# Sheet3.net
KiCad netlist of a schematic drawn in Altium Designer
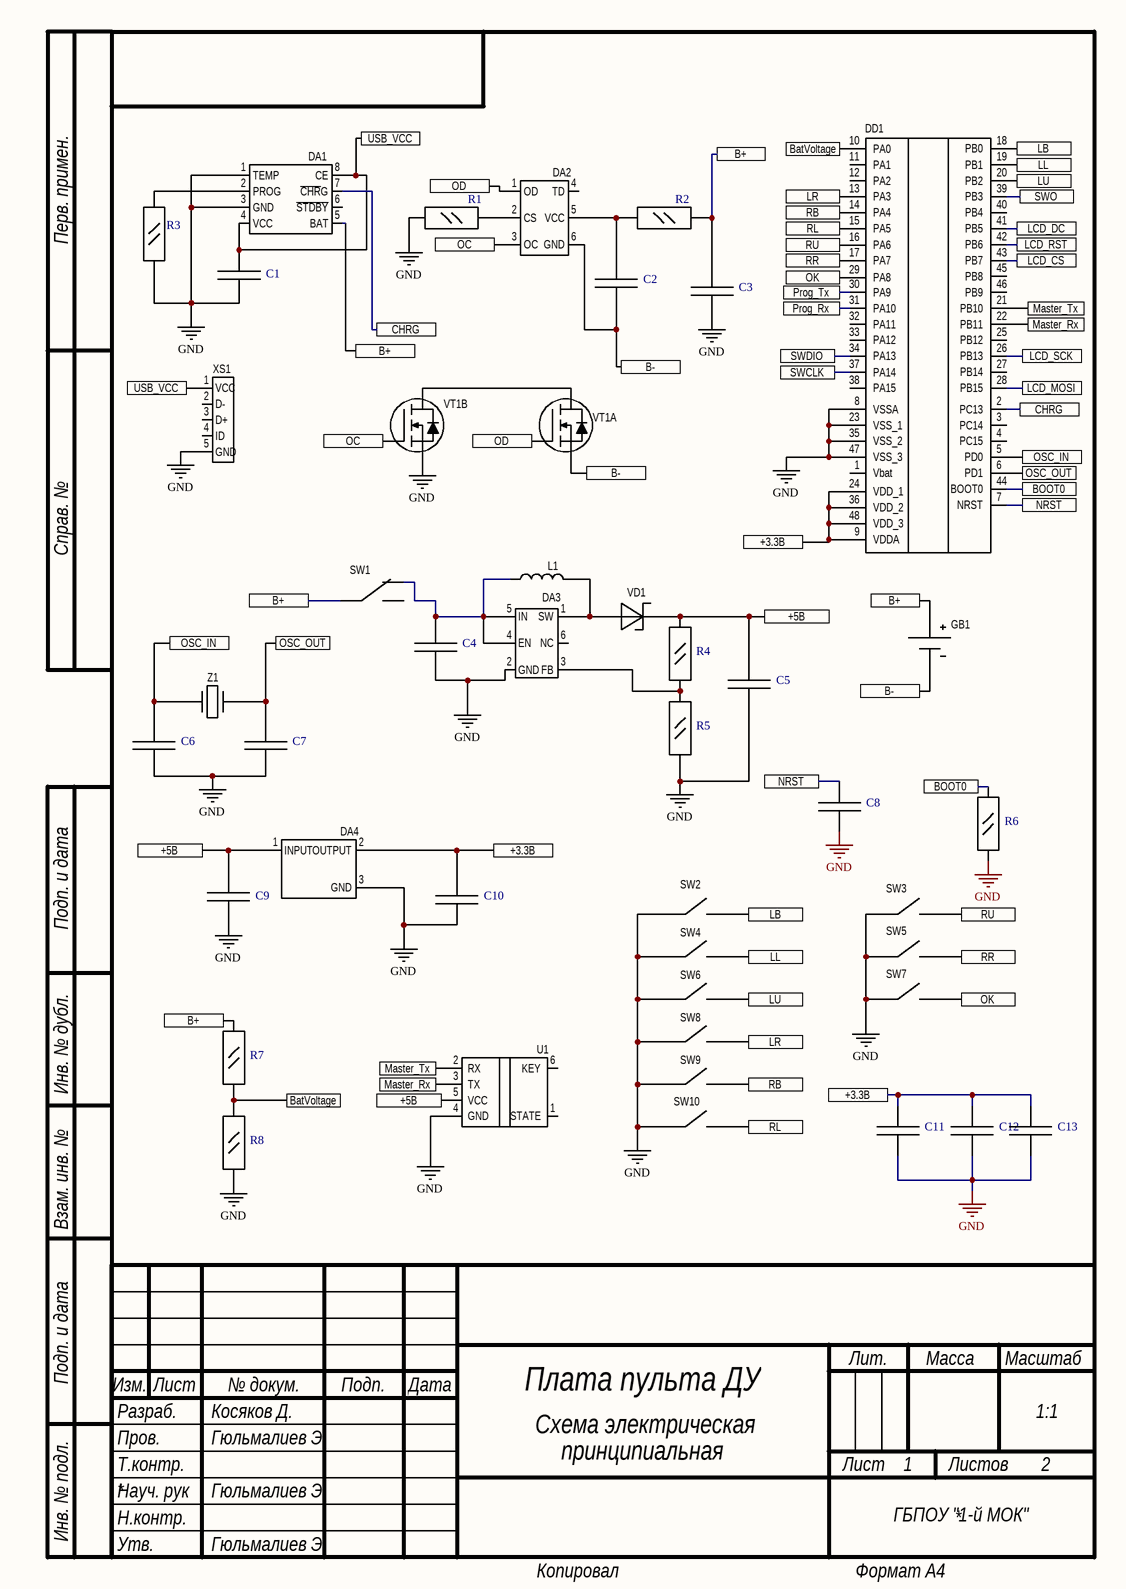
[diagram p0: Sheet3.SchDoc]

(export (version "E")
  (design (tool "Eeschema 10.0.6"))
  (components
    (comp (ref "C1") (value "0.1uF") (footprint "CAPC2112X13N") (libsource (lib "Schlib1") (part "0.1uF")))
    (comp (ref "C2") (value "0.1uF") (footprint "CAPC2112X13N") (libsource (lib "Schlib1") (part "0.1uF")))
    (comp (ref "C3") (value "10uF") (footprint "CAPC2112X13N") (libsource (lib "Schlib1") (part "0.1uF")))
    (comp (ref "C4") (value "22uF") (footprint "CAPC2112X13N") (libsource (lib "Schlib1") (part "0.1uF")))
    (comp (ref "C5") (value "22uF") (footprint "CAPC2112X13N") (libsource (lib "Schlib1") (part "0.1uF")))
    (comp (ref "C6") (value "22pF") (footprint "CAPC2112X13N") (libsource (lib "Schlib1") (part "0.1uF")))
    (comp (ref "C7") (value "22pF") (footprint "CAPC2112X13N") (libsource (lib "Schlib1") (part "0.1uF")))
    (comp (ref "C8") (value "0.1uF") (footprint "CAPC2112X13N") (libsource (lib "Schlib1") (part "0.1uF")))
    (comp (ref "C9") (value "10uF") (footprint "CAPC2112X13N") (libsource (lib "Schlib1") (part "0.1uF")))
    (comp (ref "C10") (value "10uF") (footprint "CAPC2112X13N") (libsource (lib "Schlib1") (part "0.1uF")))
    (comp (ref "C11") (value "0.1uF") (footprint "CAPC2112X13N") (libsource (lib "Schlib1") (part "0.1uF")))
    (comp (ref "C12") (value "0.1uF") (footprint "CAPC2112X13N") (libsource (lib "Schlib1") (part "0.1uF")))
    (comp (ref "C13") (value "0.1uF") (footprint "CAPC2112X13N") (libsource (lib "Schlib1") (part "0.1uF")))
    (comp (ref "DA1")
      (value "TP4056")
      (footprint "SOP127P600X173-8N")
      (libsource (lib "Schlib2") (part "TP4056"))
    )
    (comp (ref "DA2") (value "DA?") (footprint "SOT-23-6") (libsource (lib "Schlib2") (part "DW01A")))
    (comp (ref "DA3")
      (value "MT3608")
      (footprint "SOT-23-6")
      (description "DC-DC Up converter (SOT23-6)")
      (libsource (lib "Schlib2") (part "MT3608"))
    )
    (comp (ref "DA4")
      (value "NCP1117")
      (footprint "SOT230P700X180-4N")
      (libsource (lib "Schlib2") (part "NCP1117"))
    )
    (comp (ref "DD1")
      (value "STM32F103C8T6 (LQFP48)")
      (footprint "TSQFP50P900X900X160-48N")
      (libsource (lib "Schlib2") (part "STM32F103C8T6 (LQFP48)"))
    )
    (comp (ref "GB1") (value "Batt Li-On") (footprint "BATT") (libsource (lib "Schlib2") (part "Batt Li-On")))
    (comp (ref "L1") (value "22uH") (footprint "inductor SMD") (libsource (lib "Schlib2") (part "Inductor")))
    (comp (ref "R1")
      (value "1k")
      (footprint "RESC2113X06N")
      (libsource (lib "Schlib1") (part "Резистор 0805"))
    )
    (comp (ref "R2")
      (value "100")
      (footprint "RESC2113X06N")
      (libsource (lib "Schlib1") (part "Резистор 0805"))
    )
    (comp (ref "R3")
      (value "1.2k")
      (footprint "RESC2113X06N")
      (libsource (lib "Schlib1") (part "Резистор 0805"))
    )
    (comp (ref "R4")
      (value "15k")
      (footprint "RESC2113X06N")
      (libsource (lib "Schlib1") (part "Резистор 0805"))
    )
    (comp (ref "R5")
      (value "2k")
      (footprint "RESC2113X06N")
      (libsource (lib "Schlib1") (part "Резистор 0805"))
    )
    (comp (ref "R6")
      (value "100k")
      (footprint "RESC2113X06N")
      (libsource (lib "Schlib1") (part "Резистор 0805"))
    )
    (comp (ref "R7")
      (value "47k")
      (footprint "RESC2113X06N")
      (libsource (lib "Schlib1") (part "Резистор 0805"))
    )
    (comp (ref "R8")
      (value "47k")
      (footprint "RESC2113X06N")
      (libsource (lib "Schlib1") (part "Резистор 0805"))
    )
    (comp (ref "SW1") (value "SWITCH") (footprint "Switch") (libsource (lib "Schlib2") (part "SWITCH")))
    (comp (ref "SW2")
      (value "Button")
      (footprint "PCBComponent_1")
      (libsource (lib "Schlib2") (part "Button"))
    )
    (comp (ref "SW3")
      (value "Button")
      (footprint "PCBComponent_1")
      (libsource (lib "Schlib2") (part "Button"))
    )
    (comp (ref "SW4")
      (value "Button")
      (footprint "PCBComponent_1")
      (libsource (lib "Schlib2") (part "Button"))
    )
    (comp (ref "SW5")
      (value "Button")
      (footprint "PCBComponent_1")
      (libsource (lib "Schlib2") (part "Button"))
    )
    (comp (ref "SW6")
      (value "Button")
      (footprint "PCBComponent_1")
      (libsource (lib "Schlib2") (part "Button"))
    )
    (comp (ref "SW7")
      (value "Button")
      (footprint "PCBComponent_1")
      (libsource (lib "Schlib2") (part "Button"))
    )
    (comp (ref "SW8")
      (value "Button")
      (footprint "PCBComponent_1")
      (libsource (lib "Schlib2") (part "Button"))
    )
    (comp (ref "SW9")
      (value "Button")
      (footprint "PCBComponent_1")
      (libsource (lib "Schlib2") (part "Button"))
    )
    (comp (ref "SW10")
      (value "Button")
      (footprint "PCBComponent_1")
      (libsource (lib "Schlib2") (part "Button"))
    )
    (comp (ref "U1") (value "HC-05") (footprint "HC-05") (libsource (lib "Schlib1") (part "HC-05")))
    (comp (ref "VD1")
      (value "SS34")
      (footprint "SS34")
      (description "Диод Шоттки 3A 40V")
      (libsource (lib "Schlib2") (part "SS34"))
    )
    (comp (ref "VT1")
      (value "FS8205A(MOSFET,TSSOP-8)")
      (footprint "TSOP65P600X120-8N")
      (description "N-Channel MOSFET TSSOP-8")
      (libsource (lib "Schlib2") (part "FS8205A(MOSFET,TSSOP-8)"))
    )
    (comp (ref "XS1") (value "USB") (footprint "USB_Type2") (libsource (lib "Schlib1") (part "USB")))
    (comp (ref "Z1") (value "Quartz") (footprint "HC-49SM") (libsource (lib "Schlib2") (part "Quartz")))
  )
  (nets
    (net (code "1") (name "/+3.3В") (class "Default")
      (node (ref "C10") (pin "2") (pinfunction "2_2") (pintype "passive"))
      (node (ref "C11") (pin "2") (pinfunction "2_2") (pintype "passive"))
      (node (ref "C12") (pin "2") (pinfunction "2_2") (pintype "passive"))
      (node (ref "C13") (pin "2") (pinfunction "2_2") (pintype "passive"))
      (node (ref "DA4") (pin "2") (pinfunction "OUTPUT_2") (pintype "passive"))
      (node (ref "DD1") (pin "24") (pinfunction "VDD_1_24") (pintype "passive"))
      (node (ref "DD1") (pin "36") (pinfunction "VDD_2_36") (pintype "passive"))
      (node (ref "DD1") (pin "48") (pinfunction "VDD_3_48") (pintype "passive"))
      (node (ref "DD1") (pin "9") (pinfunction "VDDA_9") (pintype "passive"))
    )
    (net (code "2") (name "/+5В") (class "Default")
      (node (ref "C5") (pin "2") (pinfunction "2_2") (pintype "passive"))
      (node (ref "C9") (pin "2") (pinfunction "2_2") (pintype "passive"))
      (node (ref "DA4") (pin "1") (pinfunction "INPUT_1") (pintype "passive"))
      (node (ref "R4") (pin "2") (pinfunction "2_2") (pintype "passive"))
      (node (ref "U1") (pin "5") (pinfunction "VCC_5") (pintype "passive"))
      (node (ref "VD1") (pin "2") (pinfunction "2_2") (pintype "passive"))
    )
    (net (code "3") (name "/B+") (class "Default")
      (node (ref "C3") (pin "2") (pinfunction "2_2") (pintype "passive"))
      (node (ref "DA1") (pin "5") (pinfunction "BAT_5") (pintype "passive"))
      (node (ref "GB1") (pin "1") (pinfunction "1_1") (pintype "passive"))
      (node (ref "R2") (pin "1") (pinfunction "1_1") (pintype "passive"))
      (node (ref "R7") (pin "2") (pinfunction "2_2") (pintype "passive"))
      (node (ref "SW1") (pin "1") (pinfunction "1_1") (pintype "passive"))
    )
    (net (code "4") (name "/B-") (class "Default")
      (node (ref "C2") (pin "1") (pinfunction "1_1") (pintype "passive"))
      (node (ref "DA2") (pin "6") (pinfunction "GND_6") (pintype "passive"))
      (node (ref "GB1") (pin "2") (pinfunction "2_2") (pintype "passive"))
      (node (ref "VT1") (pin "2") (pinfunction "S1_2") (pintype "passive"))
    )
    (net (code "5") (name "/BOOT0") (class "Default")
      (node (ref "DD1") (pin "44") (pinfunction "BOOT0_44") (pintype "passive"))
      (node (ref "R6") (pin "2") (pinfunction "2_2") (pintype "passive"))
    )
    (net (code "6") (name "/BatVoltage") (class "Default")
      (node (ref "DD1") (pin "10") (pinfunction "PA0_10") (pintype "passive"))
      (node (ref "R7") (pin "1") (pinfunction "1_1") (pintype "passive"))
      (node (ref "R8") (pin "2") (pinfunction "2_2") (pintype "passive"))
    )
    (net (code "7") (name "/CHRG") (class "Default")
      (node (ref "DA1") (pin "7") (pinfunction "~{CHR}G_7") (pintype "passive"))
      (node (ref "DD1") (pin "2") (pinfunction "PC13_2") (pintype "passive"))
    )
    (net (code "8") (name "/LB") (class "Default")
      (node (ref "DD1") (pin "18") (pinfunction "PB0_18") (pintype "passive"))
      (node (ref "SW2") (pin "2") (pinfunction "2_2") (pintype "passive"))
    )
    (net (code "9") (name "/LCD_CS") (class "Default")
      (node (ref "DD1") (pin "43") (pinfunction "PB7_43") (pintype "passive"))
    )
    (net (code "10") (name "/LCD_DC") (class "Default")
      (node (ref "DD1") (pin "41") (pinfunction "PB5_41") (pintype "passive"))
    )
    (net (code "11") (name "/LCD_MOSI") (class "Default")
      (node (ref "DD1") (pin "28") (pinfunction "PB15_28") (pintype "passive"))
    )
    (net (code "12") (name "/LCD_RST") (class "Default")
      (node (ref "DD1") (pin "42") (pinfunction "PB6_42") (pintype "passive"))
    )
    (net (code "13") (name "/LCD_SCK") (class "Default")
      (node (ref "DD1") (pin "26") (pinfunction "PB13_26") (pintype "passive"))
    )
    (net (code "14") (name "/LL") (class "Default")
      (node (ref "DD1") (pin "19") (pinfunction "PB1_19") (pintype "passive"))
      (node (ref "SW4") (pin "2") (pinfunction "2_2") (pintype "passive"))
    )
    (net (code "15") (name "/LR") (class "Default")
      (node (ref "DD1") (pin "13") (pinfunction "PA3_13") (pintype "passive"))
      (node (ref "SW8") (pin "2") (pinfunction "2_2") (pintype "passive"))
    )
    (net (code "16") (name "/LU") (class "Default")
      (node (ref "DD1") (pin "20") (pinfunction "PB2_20") (pintype "passive"))
      (node (ref "SW6") (pin "2") (pinfunction "2_2") (pintype "passive"))
    )
    (net (code "17") (name "/Master_Rx") (class "Default")
      (node (ref "DD1") (pin "22") (pinfunction "PB11_22") (pintype "passive"))
      (node (ref "U1") (pin "3") (pinfunction "TX_3") (pintype "passive"))
    )
    (net (code "18") (name "/Master_Tx") (class "Default")
      (node (ref "DD1") (pin "21") (pinfunction "PB10_21") (pintype "passive"))
      (node (ref "U1") (pin "2") (pinfunction "RX_2") (pintype "passive"))
    )
    (net (code "19") (name "/NRST") (class "Default")
      (node (ref "C8") (pin "2") (pinfunction "2_2") (pintype "passive"))
      (node (ref "DD1") (pin "7") (pinfunction "NRST_7") (pintype "passive"))
    )
    (net (code "20") (name "/OC") (class "Default")
      (node (ref "DA2") (pin "3") (pinfunction "OC_3") (pintype "passive"))
      (node (ref "VT1") (pin "5") (pinfunction "G2_5") (pintype "passive"))
    )
    (net (code "21") (name "/OD") (class "Default")
      (node (ref "DA2") (pin "1") (pinfunction "OD_1") (pintype "passive"))
      (node (ref "VT1") (pin "4") (pinfunction "G1_4") (pintype "passive"))
    )
    (net (code "22") (name "/OK") (class "Default")
      (node (ref "DD1") (pin "29") (pinfunction "PA8_29") (pintype "passive"))
      (node (ref "SW7") (pin "2") (pinfunction "2_2") (pintype "passive"))
    )
    (net (code "23") (name "/OSC_IN") (class "Default")
      (node (ref "C6") (pin "2") (pinfunction "2_2") (pintype "passive"))
      (node (ref "DD1") (pin "5") (pinfunction "PD0_5") (pintype "passive"))
      (node (ref "Z1") (pin "1") (pinfunction "1_1") (pintype "passive"))
    )
    (net (code "24") (name "/OSC_OUT") (class "Default")
      (node (ref "C7") (pin "2") (pinfunction "2_2") (pintype "passive"))
      (node (ref "DD1") (pin "6") (pinfunction "PD1_6") (pintype "passive"))
      (node (ref "Z1") (pin "2") (pinfunction "2_2") (pintype "passive"))
    )
    (net (code "25") (name "/Prog_Rx") (class "Default")
      (node (ref "DD1") (pin "31") (pinfunction "PA10_31") (pintype "passive"))
    )
    (net (code "26") (name "/Prog_Tx") (class "Default")
      (node (ref "DD1") (pin "30") (pinfunction "PA9_30") (pintype "passive"))
    )
    (net (code "27") (name "/RB") (class "Default")
      (node (ref "DD1") (pin "14") (pinfunction "PA4_14") (pintype "passive"))
      (node (ref "SW9") (pin "2") (pinfunction "2_2") (pintype "passive"))
    )
    (net (code "28") (name "/RL") (class "Default")
      (node (ref "DD1") (pin "15") (pinfunction "PA5_15") (pintype "passive"))
      (node (ref "SW10") (pin "2") (pinfunction "2_2") (pintype "passive"))
    )
    (net (code "29") (name "/RR") (class "Default")
      (node (ref "DD1") (pin "17") (pinfunction "PA7_17") (pintype "passive"))
      (node (ref "SW5") (pin "2") (pinfunction "2_2") (pintype "passive"))
    )
    (net (code "30") (name "/RU") (class "Default")
      (node (ref "DD1") (pin "16") (pinfunction "PA6_16") (pintype "passive"))
      (node (ref "SW3") (pin "2") (pinfunction "2_2") (pintype "passive"))
    )
    (net (code "31") (name "/SWCLK") (class "Default")
      (node (ref "DD1") (pin "37") (pinfunction "PA14_37") (pintype "passive"))
    )
    (net (code "32") (name "/SWDIO") (class "Default")
      (node (ref "DD1") (pin "34") (pinfunction "PA13_34") (pintype "passive"))
    )
    (net (code "33") (name "/SWO") (class "Default")
      (node (ref "DD1") (pin "39") (pinfunction "PB3_39") (pintype "passive"))
    )
    (net (code "34") (name "/USB_VCC") (class "Default")
      (node (ref "C1") (pin "2") (pinfunction "2_2") (pintype "passive"))
      (node (ref "DA1") (pin "4") (pinfunction "VCC_4") (pintype "passive"))
      (node (ref "DA1") (pin "8") (pinfunction "CE_8") (pintype "passive"))
      (node (ref "XS1") (pin "1") (pinfunction "VCC_1") (pintype "passive"))
    )
    (net (code "35") (name "GND") (class "Default")
      (node (ref "C1") (pin "1") (pinfunction "1_1") (pintype "passive"))
      (node (ref "C10") (pin "1") (pinfunction "1_1") (pintype "passive"))
      (node (ref "C11") (pin "1") (pinfunction "1_1") (pintype "passive"))
      (node (ref "C12") (pin "1") (pinfunction "1_1") (pintype "passive"))
      (node (ref "C13") (pin "1") (pinfunction "1_1") (pintype "passive"))
      (node (ref "C3") (pin "1") (pinfunction "1_1") (pintype "passive"))
      (node (ref "C4") (pin "1") (pinfunction "1_1") (pintype "passive"))
      (node (ref "C5") (pin "1") (pinfunction "1_1") (pintype "passive"))
      (node (ref "C6") (pin "1") (pinfunction "1_1") (pintype "passive"))
      (node (ref "C7") (pin "1") (pinfunction "1_1") (pintype "passive"))
      (node (ref "C8") (pin "1") (pinfunction "1_1") (pintype "passive"))
      (node (ref "C9") (pin "1") (pinfunction "1_1") (pintype "passive"))
      (node (ref "DA1") (pin "1") (pinfunction "TEMP_1") (pintype "passive"))
      (node (ref "DA1") (pin "3") (pinfunction "GND_3") (pintype "passive"))
      (node (ref "DA3") (pin "2") (pinfunction "GND_2") (pintype "passive"))
      (node (ref "DA4") (pin "3") (pinfunction "GND_3") (pintype "passive"))
      (node (ref "DD1") (pin "23") (pinfunction "VSS_1_23") (pintype "passive"))
      (node (ref "DD1") (pin "35") (pinfunction "VSS_2_35") (pintype "passive"))
      (node (ref "DD1") (pin "47") (pinfunction "VSS_3_47") (pintype "passive"))
      (node (ref "DD1") (pin "8") (pinfunction "VSSA_8") (pintype "passive"))
      (node (ref "R1") (pin "2") (pinfunction "2_2") (pintype "passive"))
      (node (ref "R3") (pin "1") (pinfunction "1_1") (pintype "passive"))
      (node (ref "R5") (pin "1") (pinfunction "1_1") (pintype "passive"))
      (node (ref "R6") (pin "1") (pinfunction "1_1") (pintype "passive"))
      (node (ref "R8") (pin "1") (pinfunction "1_1") (pintype "passive"))
      (node (ref "SW10") (pin "1") (pinfunction "1_1") (pintype "passive"))
      (node (ref "SW2") (pin "1") (pinfunction "1_1") (pintype "passive"))
      (node (ref "SW3") (pin "1") (pinfunction "1_1") (pintype "passive"))
      (node (ref "SW4") (pin "1") (pinfunction "1_1") (pintype "passive"))
      (node (ref "SW5") (pin "1") (pinfunction "1_1") (pintype "passive"))
      (node (ref "SW6") (pin "1") (pinfunction "1_1") (pintype "passive"))
      (node (ref "SW7") (pin "1") (pinfunction "1_1") (pintype "passive"))
      (node (ref "SW8") (pin "1") (pinfunction "1_1") (pintype "passive"))
      (node (ref "SW9") (pin "1") (pinfunction "1_1") (pintype "passive"))
      (node (ref "U1") (pin "4") (pinfunction "GND_4") (pintype "passive"))
      (node (ref "VT1") (pin "6") (pinfunction "S2_6") (pintype "passive"))
      (node (ref "XS1") (pin "5") (pinfunction "GND_5") (pintype "passive"))
    )
    (net (code "36") (name "Net-(DA1-PROG)") (class "Default")
      (node (ref "DA1") (pin "2") (pinfunction "PROG_2") (pintype "passive"))
      (node (ref "R3") (pin "2") (pinfunction "2_2") (pintype "passive"))
    )
    (net (code "37") (name "Net-(DA2-CS)") (class "Default")
      (node (ref "DA2") (pin "2") (pinfunction "CS_2") (pintype "passive"))
      (node (ref "R1") (pin "1") (pinfunction "1_1") (pintype "passive"))
    )
    (net (code "38") (name "Net-(DA2-VCC)") (class "Default")
      (node (ref "C2") (pin "2") (pinfunction "2_2") (pintype "passive"))
      (node (ref "DA2") (pin "5") (pinfunction "VCC_5") (pintype "passive"))
      (node (ref "R2") (pin "2") (pinfunction "2_2") (pintype "passive"))
    )
    (net (code "39") (name "Net-(DA3-EN)") (class "Default")
      (node (ref "C4") (pin "2") (pinfunction "2_2") (pintype "passive"))
      (node (ref "DA3") (pin "4") (pinfunction "EN_4") (pintype "passive"))
      (node (ref "DA3") (pin "5") (pinfunction "IN_5") (pintype "passive"))
      (node (ref "L1") (pin "1") (pinfunction "1_1") (pintype "passive"))
      (node (ref "SW1") (pin "2") (pinfunction "2_2") (pintype "passive"))
    )
    (net (code "40") (name "Net-(DA3-FB)") (class "Default")
      (node (ref "DA3") (pin "3") (pinfunction "FB_3") (pintype "passive"))
      (node (ref "R4") (pin "1") (pinfunction "1_1") (pintype "passive"))
      (node (ref "R5") (pin "2") (pinfunction "2_2") (pintype "passive"))
    )
    (net (code "41") (name "Net-(DA3-SW)") (class "Default")
      (node (ref "DA3") (pin "1") (pinfunction "SW_1") (pintype "passive"))
      (node (ref "L1") (pin "2") (pinfunction "2_2") (pintype "passive"))
      (node (ref "VD1") (pin "1") (pinfunction "1_1") (pintype "passive"))
    )
    (net (code "42") (name "Net-(VT1A-D12)") (class "Default")
      (node (ref "VT1") (pin "1") (pinfunction "D12_1") (pintype "passive"))
      (node (ref "VT1") (pin "8") (pinfunction "D12_8") (pintype "passive"))
    )
    (net (code "43") (name "unconnected-(DA1-~{STDBY}-Pad6)") (class "Default")
      (node (ref "DA1") (pin "6") (pinfunction "~{STDBY}_6") (pintype "passive"))
    )
    (net (code "44") (name "unconnected-(DA2-TD-Pad4)") (class "Default")
      (node (ref "DA2") (pin "4") (pinfunction "TD_4") (pintype "passive"))
    )
    (net (code "45") (name "unconnected-(DA3-NC-Pad6)") (class "Default")
      (node (ref "DA3") (pin "6") (pinfunction "NC_6") (pintype "passive"))
    )
    (net (code "46") (name "unconnected-(DD1-PA1-Pad11)") (class "Default")
      (node (ref "DD1") (pin "11") (pinfunction "PA1_11") (pintype "passive"))
    )
    (net (code "47") (name "unconnected-(DD1-PA2-Pad12)") (class "Default")
      (node (ref "DD1") (pin "12") (pinfunction "PA2_12") (pintype "passive"))
    )
    (net (code "48") (name "unconnected-(DD1-PA11-Pad32)") (class "Default")
      (node (ref "DD1") (pin "32") (pinfunction "PA11_32") (pintype "passive"))
    )
    (net (code "49") (name "unconnected-(DD1-PA12-Pad33)") (class "Default")
      (node (ref "DD1") (pin "33") (pinfunction "PA12_33") (pintype "passive"))
    )
    (net (code "50") (name "unconnected-(DD1-PA15-Pad38)") (class "Default")
      (node (ref "DD1") (pin "38") (pinfunction "PA15_38") (pintype "passive"))
    )
    (net (code "51") (name "unconnected-(DD1-PB4-Pad40)") (class "Default")
      (node (ref "DD1") (pin "40") (pinfunction "PB4_40") (pintype "passive"))
    )
    (net (code "52") (name "unconnected-(DD1-PB8-Pad45)") (class "Default")
      (node (ref "DD1") (pin "45") (pinfunction "PB8_45") (pintype "passive"))
    )
    (net (code "53") (name "unconnected-(DD1-PB9-Pad46)") (class "Default")
      (node (ref "DD1") (pin "46") (pinfunction "PB9_46") (pintype "passive"))
    )
    (net (code "54") (name "unconnected-(DD1-PB12-Pad25)") (class "Default")
      (node (ref "DD1") (pin "25") (pinfunction "PB12_25") (pintype "passive"))
    )
    (net (code "55") (name "unconnected-(DD1-PB14-Pad27)") (class "Default")
      (node (ref "DD1") (pin "27") (pinfunction "PB14_27") (pintype "passive"))
    )
    (net (code "56") (name "unconnected-(DD1-PC14-Pad3)") (class "Default")
      (node (ref "DD1") (pin "3") (pinfunction "PC14_3") (pintype "passive"))
    )
    (net (code "57") (name "unconnected-(DD1-PC15-Pad4)") (class "Default")
      (node (ref "DD1") (pin "4") (pinfunction "PC15_4") (pintype "passive"))
    )
    (net (code "58") (name "unconnected-(DD1-Vbat-Pad1)") (class "Default")
      (node (ref "DD1") (pin "1") (pinfunction "Vbat_1") (pintype "passive"))
    )
    (net (code "59") (name "unconnected-(SW1-Pad3)") (class "Default")
      (node (ref "SW1") (pin "3") (pinfunction "3_3") (pintype "passive"))
    )
    (net (code "60") (name "unconnected-(U1-KEY-Pad6)") (class "Default")
      (node (ref "U1") (pin "6") (pinfunction "KEY_6") (pintype "passive"))
    )
    (net (code "61") (name "unconnected-(U1-STATE-Pad1)") (class "Default")
      (node (ref "U1") (pin "1") (pinfunction "STATE_1") (pintype "passive"))
    )
    (net (code "62") (name "unconnected-(XS1-D+-Pad3)") (class "Default")
      (node (ref "XS1") (pin "3") (pinfunction "D+_3") (pintype "passive"))
    )
    (net (code "63") (name "unconnected-(XS1-D--Pad2)") (class "Default")
      (node (ref "XS1") (pin "2") (pinfunction "D-_2") (pintype "passive"))
    )
    (net (code "64") (name "unconnected-(XS1-ID-Pad4)") (class "Default")
      (node (ref "XS1") (pin "4") (pinfunction "ID_4") (pintype "passive"))
    )
  )
)
